# SPI_Switch.net
KiCad netlist of a schematic drawn in EAGLE
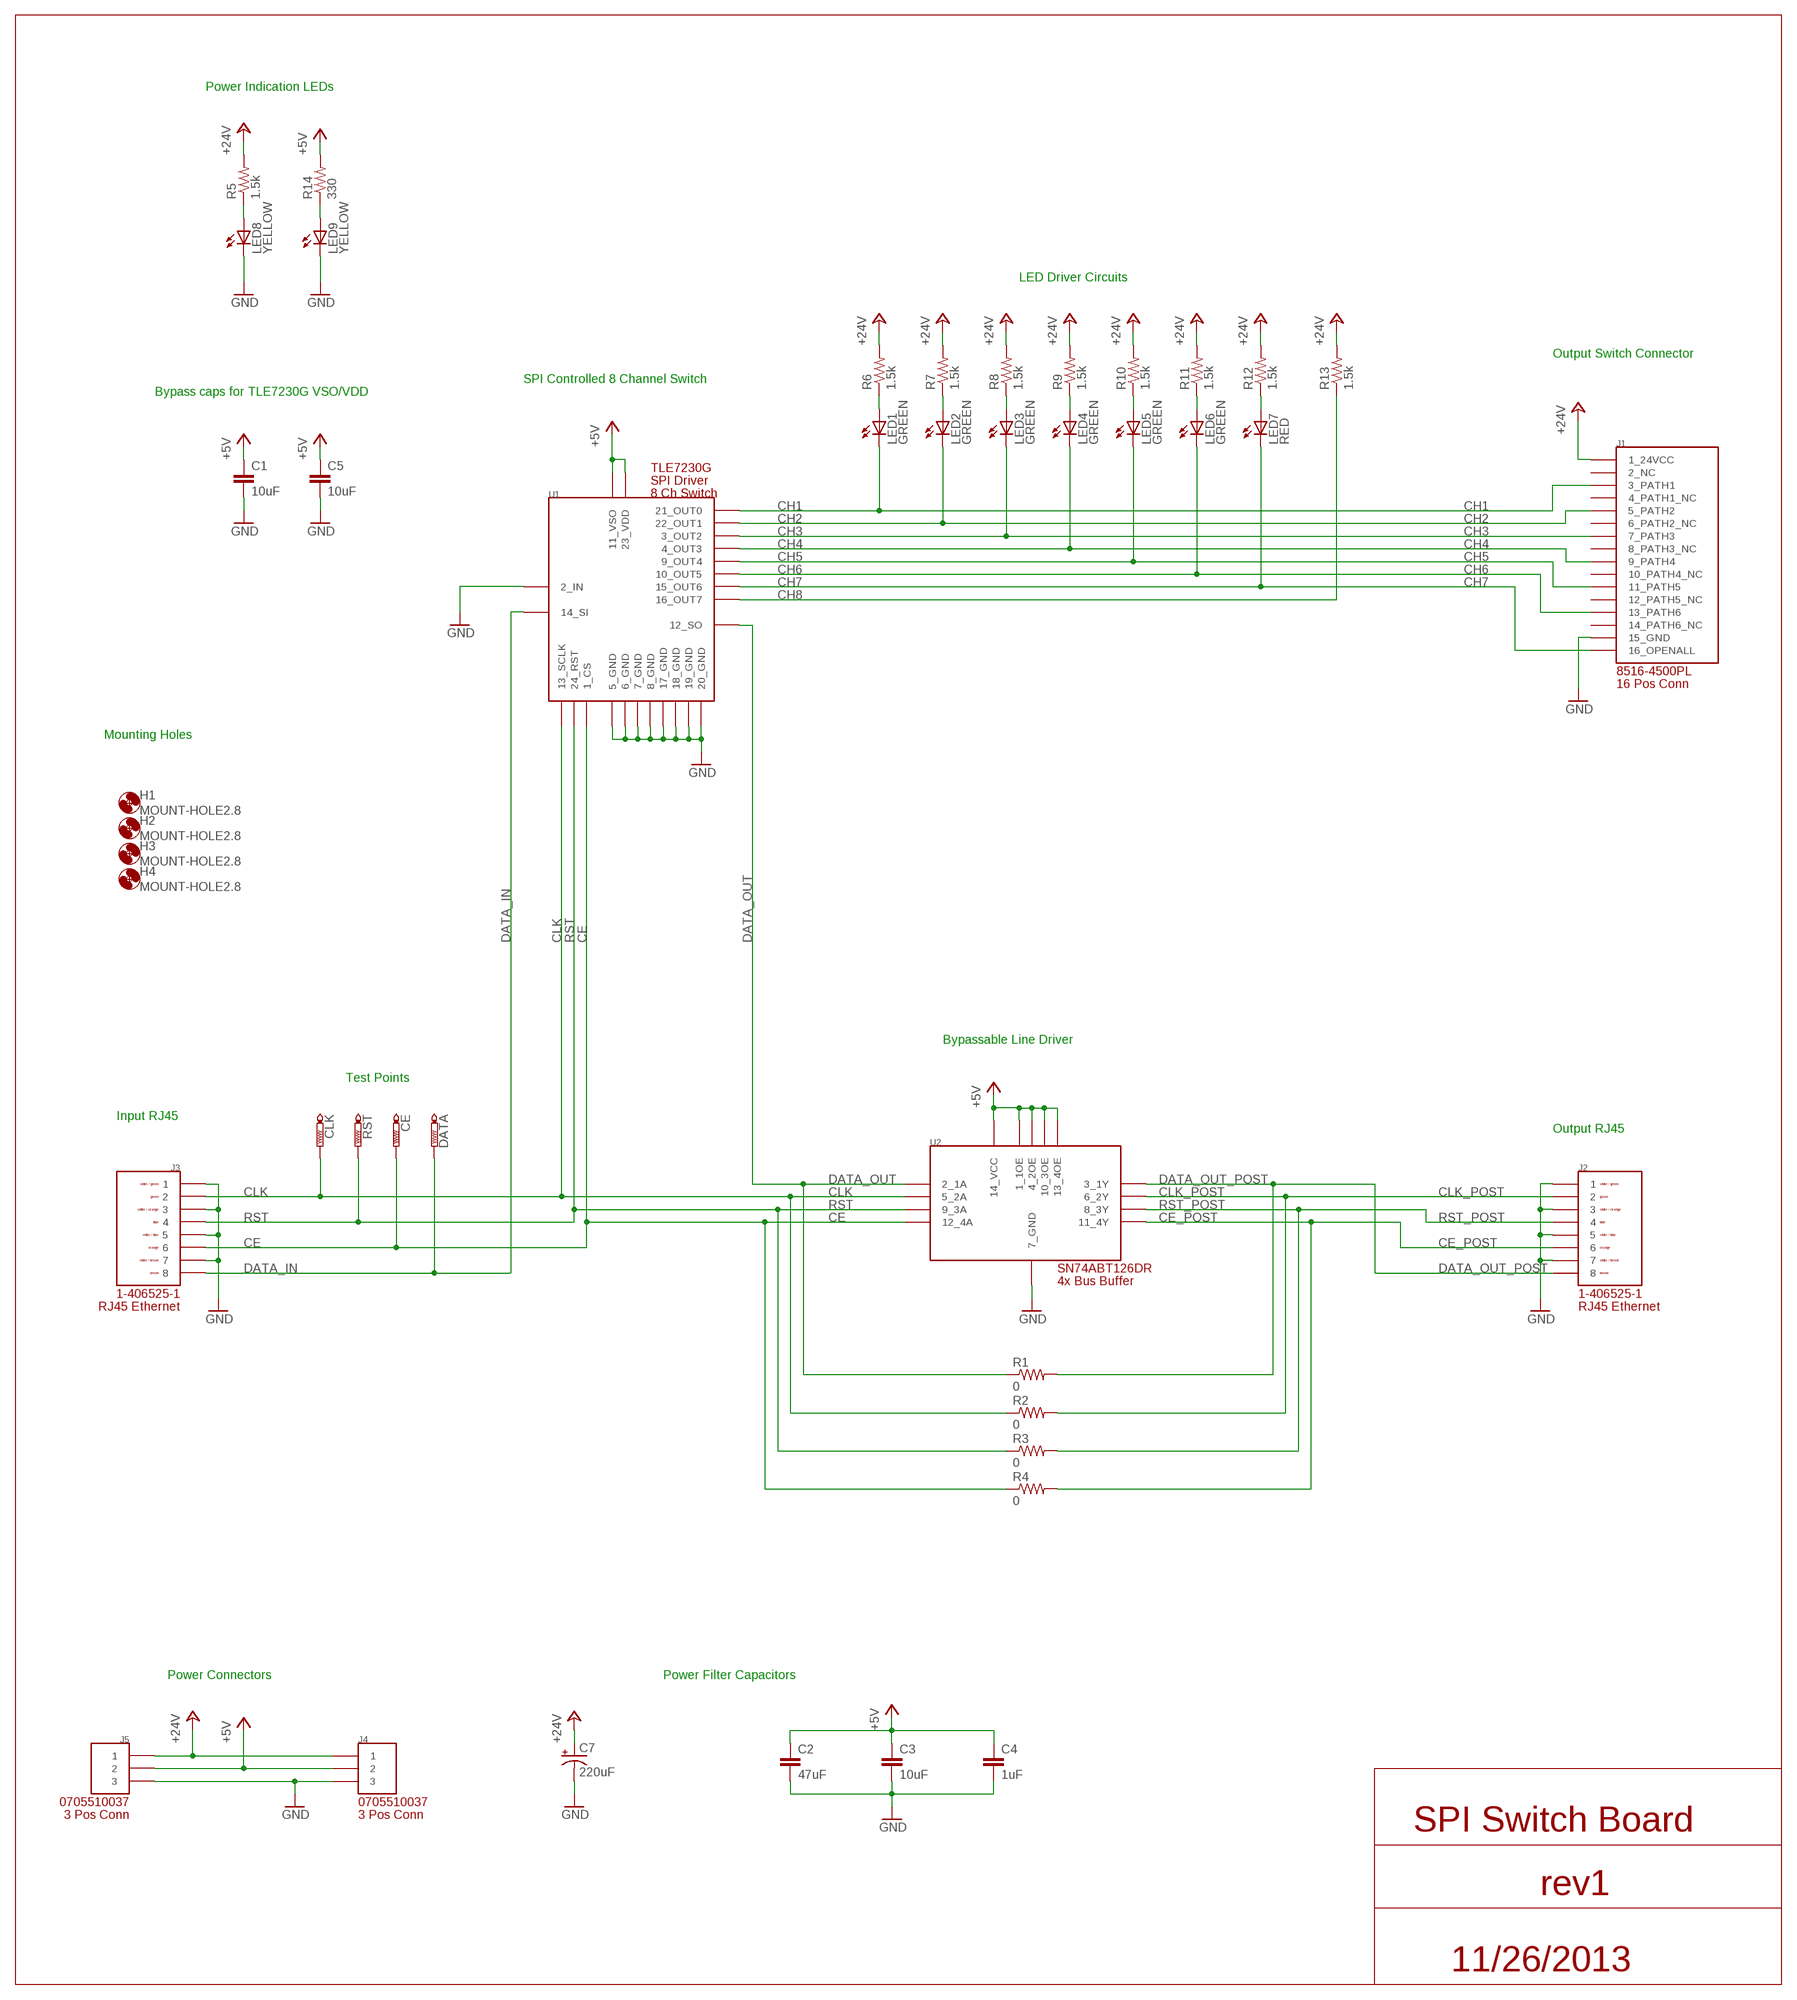
[diagram p0: schematic, sheet 1]

(export (version "E")
  (design (tool "Eeschema 10.0.6"))
  (components
    (comp (ref "C1")
      (value "10uF")
      (footprint "eagle-import:0805")
      (libsource (lib "eagle-import") (part "CAP0805"))
    )
    (comp (ref "C2")
      (value "47uF")
      (footprint "eagle-import:0805")
      (libsource (lib "eagle-import") (part "CAP0805"))
    )
    (comp (ref "C3")
      (value "10uF")
      (footprint "eagle-import:0805")
      (libsource (lib "eagle-import") (part "CAP0805"))
    )
    (comp (ref "C4")
      (value "1uF")
      (footprint "eagle-import:0805")
      (libsource (lib "eagle-import") (part "CAP0805"))
    )
    (comp (ref "C5")
      (value "10uF")
      (footprint "eagle-import:0805")
      (libsource (lib "eagle-import") (part "CAP0805"))
    )
    (comp (ref "C7")
      (value "220uF")
      (footprint "eagle-import:PANASONIC_E")
      (libsource (lib "eagle-import") (part "CAP_POLE"))
    )
    (comp (ref "CE")
      (value "PTR1PAD1-13")
      (footprint "eagle-import:P1-13")
      (libsource (lib "eagle-import") (part "PTR1PAD1-13"))
    )
    (comp (ref "CLK")
      (value "PTR1PAD1-13")
      (footprint "eagle-import:P1-13")
      (libsource (lib "eagle-import") (part "PTR1PAD1-13"))
    )
    (comp (ref "DATA")
      (value "PTR1PAD1-13")
      (footprint "eagle-import:P1-13")
      (libsource (lib "eagle-import") (part "PTR1PAD1-13"))
    )
    (comp (ref "H1")
      (value "MOUNT-HOLE2.8")
      (footprint "eagle-import:2,8")
      (libsource (lib "eagle-import") (part "MOUNT-HOLE2.8"))
    )
    (comp (ref "H2")
      (value "MOUNT-HOLE2.8")
      (footprint "eagle-import:2,8")
      (libsource (lib "eagle-import") (part "MOUNT-HOLE2.8"))
    )
    (comp (ref "H3")
      (value "MOUNT-HOLE2.8")
      (footprint "eagle-import:2,8")
      (libsource (lib "eagle-import") (part "MOUNT-HOLE2.8"))
    )
    (comp (ref "H4")
      (value "MOUNT-HOLE2.8")
      (footprint "eagle-import:2,8")
      (libsource (lib "eagle-import") (part "MOUNT-HOLE2.8"))
    )
    (comp (ref "J1")
      (value "8516-4500PL")
      (footprint "eagle-import:8516-4500PL")
      (libsource (lib "eagle-import") (part "8516-4500PL"))
    )
    (comp (ref "J2")
      (value "1-406525-1")
      (footprint "eagle-import:1-406525-1")
      (libsource (lib "eagle-import") (part "1-406525-1"))
    )
    (comp (ref "J3")
      (value "1-406525-1")
      (footprint "eagle-import:1-406525-1")
      (libsource (lib "eagle-import") (part "1-406525-1"))
    )
    (comp (ref "J4")
      (value "0705510037")
      (footprint "eagle-import:0705510037")
      (libsource (lib "eagle-import") (part "0705510037"))
    )
    (comp (ref "J5")
      (value "0705510037")
      (footprint "eagle-import:0705510037")
      (libsource (lib "eagle-import") (part "0705510037"))
    )
    (comp (ref "LED1")
      (value "GREEN")
      (footprint "eagle-import:LED-1206")
      (libsource (lib "eagle-import") (part "LED1206"))
    )
    (comp (ref "LED2")
      (value "GREEN")
      (footprint "eagle-import:LED-1206")
      (libsource (lib "eagle-import") (part "LED1206"))
    )
    (comp (ref "LED3")
      (value "GREEN")
      (footprint "eagle-import:LED-1206")
      (libsource (lib "eagle-import") (part "LED1206"))
    )
    (comp (ref "LED4")
      (value "GREEN")
      (footprint "eagle-import:LED-1206")
      (libsource (lib "eagle-import") (part "LED1206"))
    )
    (comp (ref "LED5")
      (value "GREEN")
      (footprint "eagle-import:LED-1206")
      (libsource (lib "eagle-import") (part "LED1206"))
    )
    (comp (ref "LED6")
      (value "GREEN")
      (footprint "eagle-import:LED-1206")
      (libsource (lib "eagle-import") (part "LED1206"))
    )
    (comp (ref "LED7")
      (value "RED")
      (footprint "eagle-import:LED-1206")
      (libsource (lib "eagle-import") (part "LED1206"))
    )
    (comp (ref "LED8")
      (value "YELLOW")
      (footprint "eagle-import:LED-1206")
      (libsource (lib "eagle-import") (part "LED1206"))
    )
    (comp (ref "LED9")
      (value "YELLOW")
      (footprint "eagle-import:LED-1206")
      (libsource (lib "eagle-import") (part "LED1206"))
    )
    (comp (ref "R1")
      (value "0")
      (footprint "eagle-import:0805")
      (libsource (lib "eagle-import") (part "RESISTOR0805-RES"))
    )
    (comp (ref "R2")
      (value "0")
      (footprint "eagle-import:0805")
      (libsource (lib "eagle-import") (part "RESISTOR0805-RES"))
    )
    (comp (ref "R3")
      (value "0")
      (footprint "eagle-import:0805")
      (libsource (lib "eagle-import") (part "RESISTOR0805-RES"))
    )
    (comp (ref "R4")
      (value "0")
      (footprint "eagle-import:0805")
      (libsource (lib "eagle-import") (part "RESISTOR0805-RES"))
    )
    (comp (ref "R5")
      (value "1.5k")
      (footprint "eagle-import:1206")
      (libsource (lib "eagle-import") (part "RESISTOR1206"))
    )
    (comp (ref "R6")
      (value "1.5k")
      (footprint "eagle-import:1206")
      (libsource (lib "eagle-import") (part "RESISTOR1206"))
    )
    (comp (ref "R7")
      (value "1.5k")
      (footprint "eagle-import:1206")
      (libsource (lib "eagle-import") (part "RESISTOR1206"))
    )
    (comp (ref "R8")
      (value "1.5k")
      (footprint "eagle-import:1206")
      (libsource (lib "eagle-import") (part "RESISTOR1206"))
    )
    (comp (ref "R9")
      (value "1.5k")
      (footprint "eagle-import:1206")
      (libsource (lib "eagle-import") (part "RESISTOR1206"))
    )
    (comp (ref "R10")
      (value "1.5k")
      (footprint "eagle-import:1206")
      (libsource (lib "eagle-import") (part "RESISTOR1206"))
    )
    (comp (ref "R11")
      (value "1.5k")
      (footprint "eagle-import:1206")
      (libsource (lib "eagle-import") (part "RESISTOR1206"))
    )
    (comp (ref "R12")
      (value "1.5k")
      (footprint "eagle-import:1206")
      (libsource (lib "eagle-import") (part "RESISTOR1206"))
    )
    (comp (ref "R13")
      (value "1.5k")
      (footprint "eagle-import:1206")
      (libsource (lib "eagle-import") (part "RESISTOR1206"))
    )
    (comp (ref "R14")
      (value "330")
      (footprint "eagle-import:0805")
      (libsource (lib "eagle-import") (part "RESISTOR0805-RES"))
    )
    (comp (ref "RST")
      (value "PTR1PAD1-13")
      (footprint "eagle-import:P1-13")
      (libsource (lib "eagle-import") (part "PTR1PAD1-13"))
    )
    (comp (ref "U1")
      (value "TLE7230G")
      (footprint "eagle-import:TLE7230G")
      (libsource (lib "eagle-import") (part "TLE7230G"))
    )
    (comp (ref "U2")
      (value "SN74ABT126")
      (footprint "eagle-import:SN74ABT126")
      (libsource (lib "eagle-import") (part "SN74ABT126"))
    )
  )
  (nets
    (net (code "1") (name "+5V") (class "Default")
      (node (ref "C1") (pin "1") (pinfunction "1_1") (pintype "passive"))
      (node (ref "C2") (pin "1") (pinfunction "1_1") (pintype "passive"))
      (node (ref "C3") (pin "1") (pinfunction "1_1") (pintype "passive"))
      (node (ref "C4") (pin "1") (pinfunction "1_1") (pintype "passive"))
      (node (ref "C5") (pin "1") (pinfunction "1_1") (pintype "passive"))
      (node (ref "J4") (pin "P$2") (pinfunction "2_P$2") (pintype "bidirectional"))
      (node (ref "J5") (pin "P$2") (pinfunction "2_P$2") (pintype "bidirectional"))
      (node (ref "R14") (pin "2") (pinfunction "2_2") (pintype "passive"))
      (node (ref "U1") (pin "11") (pinfunction "11_VSO_11") (pintype "bidirectional"))
      (node (ref "U1") (pin "23") (pinfunction "23_VDD_23") (pintype "bidirectional"))
      (node (ref "U2") (pin "1") (pinfunction "1_1OE_1") (pintype "bidirectional"))
      (node (ref "U2") (pin "10") (pinfunction "10_3OE_10") (pintype "bidirectional"))
      (node (ref "U2") (pin "13") (pinfunction "13_4OE_13") (pintype "bidirectional"))
      (node (ref "U2") (pin "14") (pinfunction "14_VCC_14") (pintype "bidirectional"))
      (node (ref "U2") (pin "4") (pinfunction "4_2OE_4") (pintype "bidirectional"))
    )
    (net (code "2") (name "+24V") (class "Default")
      (node (ref "C7") (pin "+") (pinfunction "+_+") (pintype "passive"))
      (node (ref "J1") (pin "P$1") (pinfunction "1_24VCC_P$1") (pintype "bidirectional"))
      (node (ref "J4") (pin "P$1") (pinfunction "1_P$1") (pintype "bidirectional"))
      (node (ref "J5") (pin "P$1") (pinfunction "1_P$1") (pintype "bidirectional"))
      (node (ref "R10") (pin "2") (pinfunction "2_2") (pintype "passive"))
      (node (ref "R11") (pin "2") (pinfunction "2_2") (pintype "passive"))
      (node (ref "R12") (pin "2") (pinfunction "2_2") (pintype "passive"))
      (node (ref "R13") (pin "2") (pinfunction "2_2") (pintype "passive"))
      (node (ref "R5") (pin "2") (pinfunction "2_2") (pintype "passive"))
      (node (ref "R6") (pin "2") (pinfunction "2_2") (pintype "passive"))
      (node (ref "R7") (pin "2") (pinfunction "2_2") (pintype "passive"))
      (node (ref "R8") (pin "2") (pinfunction "2_2") (pintype "passive"))
      (node (ref "R9") (pin "2") (pinfunction "2_2") (pintype "passive"))
    )
    (net (code "3") (name "/CE") (class "Default")
      (node (ref "CE") (pin "TP") (pinfunction "TP_TP") (pintype "input"))
      (node (ref "J3") (pin "P$6") (pinfunction "6_P$6") (pintype "bidirectional"))
      (node (ref "R4") (pin "1") (pinfunction "1_1") (pintype "passive"))
      (node (ref "U1") (pin "1") (pinfunction "1_CS_1") (pintype "bidirectional"))
      (node (ref "U2") (pin "12") (pinfunction "12_4A_12") (pintype "bidirectional"))
    )
    (net (code "4") (name "/CE_POST") (class "Default")
      (node (ref "J2") (pin "P$6") (pinfunction "6_P$6") (pintype "bidirectional"))
      (node (ref "R4") (pin "2") (pinfunction "2_2") (pintype "passive"))
      (node (ref "U2") (pin "11") (pinfunction "11_4Y_11") (pintype "bidirectional"))
    )
    (net (code "5") (name "/CH1") (class "Default")
      (node (ref "J1") (pin "P$3") (pinfunction "3_PATH1_P$3") (pintype "bidirectional"))
      (node (ref "LED1") (pin "C") (pinfunction "C_C") (pintype "passive"))
      (node (ref "U1") (pin "21") (pinfunction "21_OUT0_21") (pintype "bidirectional"))
    )
    (net (code "6") (name "/CH2") (class "Default")
      (node (ref "J1") (pin "P$5") (pinfunction "5_PATH2_P$5") (pintype "bidirectional"))
      (node (ref "LED2") (pin "C") (pinfunction "C_C") (pintype "passive"))
      (node (ref "U1") (pin "22") (pinfunction "22_OUT1_22") (pintype "bidirectional"))
    )
    (net (code "7") (name "/CH3") (class "Default")
      (node (ref "J1") (pin "P$7") (pinfunction "7_PATH3_P$7") (pintype "bidirectional"))
      (node (ref "LED3") (pin "C") (pinfunction "C_C") (pintype "passive"))
      (node (ref "U1") (pin "3") (pinfunction "3_OUT2_3") (pintype "bidirectional"))
    )
    (net (code "8") (name "/CH4") (class "Default")
      (node (ref "J1") (pin "P$9") (pinfunction "9_PATH4_P$9") (pintype "bidirectional"))
      (node (ref "LED4") (pin "C") (pinfunction "C_C") (pintype "passive"))
      (node (ref "U1") (pin "4") (pinfunction "4_OUT3_4") (pintype "bidirectional"))
    )
    (net (code "9") (name "/CH5") (class "Default")
      (node (ref "J1") (pin "P$11") (pinfunction "11_PATH5_P$11") (pintype "bidirectional"))
      (node (ref "LED5") (pin "C") (pinfunction "C_C") (pintype "passive"))
      (node (ref "U1") (pin "9") (pinfunction "9_OUT4_9") (pintype "bidirectional"))
    )
    (net (code "10") (name "/CH6") (class "Default")
      (node (ref "J1") (pin "P$13") (pinfunction "13_PATH6_P$13") (pintype "bidirectional"))
      (node (ref "LED6") (pin "C") (pinfunction "C_C") (pintype "passive"))
      (node (ref "U1") (pin "10") (pinfunction "10_OUT5_10") (pintype "bidirectional"))
    )
    (net (code "11") (name "/CH7") (class "Default")
      (node (ref "J1") (pin "P$16") (pinfunction "16_OPENALL_P$16") (pintype "bidirectional"))
      (node (ref "LED7") (pin "C") (pinfunction "C_C") (pintype "passive"))
      (node (ref "U1") (pin "15") (pinfunction "15_OUT6_15") (pintype "bidirectional"))
    )
    (net (code "12") (name "/CH8") (class "Default")
      (node (ref "R13") (pin "1") (pinfunction "1_1") (pintype "passive"))
      (node (ref "U1") (pin "16") (pinfunction "16_OUT7_16") (pintype "bidirectional"))
    )
    (net (code "13") (name "/CLK") (class "Default")
      (node (ref "CLK") (pin "TP") (pinfunction "TP_TP") (pintype "input"))
      (node (ref "J3") (pin "P$2") (pinfunction "2_P$2") (pintype "bidirectional"))
      (node (ref "R2") (pin "1") (pinfunction "1_1") (pintype "passive"))
      (node (ref "U1") (pin "13") (pinfunction "13_SCLK_13") (pintype "bidirectional"))
      (node (ref "U2") (pin "5") (pinfunction "5_2A_5") (pintype "bidirectional"))
    )
    (net (code "14") (name "/CLK_POST") (class "Default")
      (node (ref "J2") (pin "P$2") (pinfunction "2_P$2") (pintype "bidirectional"))
      (node (ref "R2") (pin "2") (pinfunction "2_2") (pintype "passive"))
      (node (ref "U2") (pin "6") (pinfunction "6_2Y_6") (pintype "bidirectional"))
    )
    (net (code "15") (name "/DATA_IN") (class "Default")
      (node (ref "DATA") (pin "TP") (pinfunction "TP_TP") (pintype "input"))
      (node (ref "J3") (pin "P$8") (pinfunction "8_P$8") (pintype "bidirectional"))
      (node (ref "U1") (pin "14") (pinfunction "14_SI_14") (pintype "bidirectional"))
    )
    (net (code "16") (name "/DATA_OUT") (class "Default")
      (node (ref "R1") (pin "1") (pinfunction "1_1") (pintype "passive"))
      (node (ref "U1") (pin "12") (pinfunction "12_SO_12") (pintype "bidirectional"))
      (node (ref "U2") (pin "2") (pinfunction "2_1A_2") (pintype "bidirectional"))
    )
    (net (code "17") (name "/DATA_OUT_POST") (class "Default")
      (node (ref "J2") (pin "P$8") (pinfunction "8_P$8") (pintype "bidirectional"))
      (node (ref "R1") (pin "2") (pinfunction "2_2") (pintype "passive"))
      (node (ref "U2") (pin "3") (pinfunction "3_1Y_3") (pintype "bidirectional"))
    )
    (net (code "18") (name "/RST") (class "Default")
      (node (ref "J3") (pin "P$4") (pinfunction "4_P$4") (pintype "bidirectional"))
      (node (ref "R3") (pin "1") (pinfunction "1_1") (pintype "passive"))
      (node (ref "RST") (pin "TP") (pinfunction "TP_TP") (pintype "input"))
      (node (ref "U1") (pin "24") (pinfunction "24_RST_24") (pintype "bidirectional"))
      (node (ref "U2") (pin "9") (pinfunction "9_3A_9") (pintype "bidirectional"))
    )
    (net (code "19") (name "/RST_POST") (class "Default")
      (node (ref "J2") (pin "P$4") (pinfunction "4_P$4") (pintype "bidirectional"))
      (node (ref "R3") (pin "2") (pinfunction "2_2") (pintype "passive"))
      (node (ref "U2") (pin "8") (pinfunction "8_3Y_8") (pintype "bidirectional"))
    )
    (net (code "20") (name "GND") (class "Default")
      (node (ref "C1") (pin "2") (pinfunction "2_2") (pintype "passive"))
      (node (ref "C2") (pin "2") (pinfunction "2_2") (pintype "passive"))
      (node (ref "C3") (pin "2") (pinfunction "2_2") (pintype "passive"))
      (node (ref "C4") (pin "2") (pinfunction "2_2") (pintype "passive"))
      (node (ref "C5") (pin "2") (pinfunction "2_2") (pintype "passive"))
      (node (ref "C7") (pin "-") (pinfunction "-_-") (pintype "passive"))
      (node (ref "J1") (pin "P$15") (pinfunction "15_GND_P$15") (pintype "bidirectional"))
      (node (ref "J2") (pin "P$1") (pinfunction "1_P$1") (pintype "bidirectional"))
      (node (ref "J2") (pin "P$3") (pinfunction "3_P$3") (pintype "bidirectional"))
      (node (ref "J2") (pin "P$5") (pinfunction "5_P$5") (pintype "bidirectional"))
      (node (ref "J2") (pin "P$7") (pinfunction "7_P$7") (pintype "bidirectional"))
      (node (ref "J3") (pin "P$1") (pinfunction "1_P$1") (pintype "bidirectional"))
      (node (ref "J3") (pin "P$3") (pinfunction "3_P$3") (pintype "bidirectional"))
      (node (ref "J3") (pin "P$5") (pinfunction "5_P$5") (pintype "bidirectional"))
      (node (ref "J3") (pin "P$7") (pinfunction "7_P$7") (pintype "bidirectional"))
      (node (ref "J4") (pin "P$3") (pinfunction "3_P$3") (pintype "bidirectional"))
      (node (ref "J5") (pin "P$3") (pinfunction "3_P$3") (pintype "bidirectional"))
      (node (ref "LED8") (pin "C") (pinfunction "C_C") (pintype "passive"))
      (node (ref "LED9") (pin "C") (pinfunction "C_C") (pintype "passive"))
      (node (ref "U1") (pin "17") (pinfunction "17_GND_17") (pintype "bidirectional"))
      (node (ref "U1") (pin "18") (pinfunction "18_GND_18") (pintype "bidirectional"))
      (node (ref "U1") (pin "19") (pinfunction "19_GND_19") (pintype "bidirectional"))
      (node (ref "U1") (pin "2") (pinfunction "2_IN_2") (pintype "bidirectional"))
      (node (ref "U1") (pin "20") (pinfunction "20_GND_20") (pintype "bidirectional"))
      (node (ref "U1") (pin "5") (pinfunction "5_GND_5") (pintype "bidirectional"))
      (node (ref "U1") (pin "6") (pinfunction "6_GND_6") (pintype "bidirectional"))
      (node (ref "U1") (pin "7") (pinfunction "7_GND_7") (pintype "bidirectional"))
      (node (ref "U1") (pin "8") (pinfunction "8_GND_8") (pintype "bidirectional"))
      (node (ref "U2") (pin "7") (pinfunction "7_GND_7") (pintype "bidirectional"))
    )
    (net (code "21") (name "Net-(LED1-PadA)") (class "Default")
      (node (ref "LED1") (pin "A") (pinfunction "A_A") (pintype "passive"))
      (node (ref "R6") (pin "1") (pinfunction "1_1") (pintype "passive"))
    )
    (net (code "22") (name "Net-(LED2-PadA)") (class "Default")
      (node (ref "LED2") (pin "A") (pinfunction "A_A") (pintype "passive"))
      (node (ref "R7") (pin "1") (pinfunction "1_1") (pintype "passive"))
    )
    (net (code "23") (name "Net-(LED3-PadA)") (class "Default")
      (node (ref "LED3") (pin "A") (pinfunction "A_A") (pintype "passive"))
      (node (ref "R8") (pin "1") (pinfunction "1_1") (pintype "passive"))
    )
    (net (code "24") (name "Net-(LED4-PadA)") (class "Default")
      (node (ref "LED4") (pin "A") (pinfunction "A_A") (pintype "passive"))
      (node (ref "R9") (pin "1") (pinfunction "1_1") (pintype "passive"))
    )
    (net (code "25") (name "Net-(LED5-PadA)") (class "Default")
      (node (ref "LED5") (pin "A") (pinfunction "A_A") (pintype "passive"))
      (node (ref "R10") (pin "1") (pinfunction "1_1") (pintype "passive"))
    )
    (net (code "26") (name "Net-(LED6-PadA)") (class "Default")
      (node (ref "LED6") (pin "A") (pinfunction "A_A") (pintype "passive"))
      (node (ref "R11") (pin "1") (pinfunction "1_1") (pintype "passive"))
    )
    (net (code "27") (name "Net-(LED7-PadA)") (class "Default")
      (node (ref "LED7") (pin "A") (pinfunction "A_A") (pintype "passive"))
      (node (ref "R12") (pin "1") (pinfunction "1_1") (pintype "passive"))
    )
    (net (code "28") (name "Net-(LED8-PadA)") (class "Default")
      (node (ref "LED8") (pin "A") (pinfunction "A_A") (pintype "passive"))
      (node (ref "R5") (pin "1") (pinfunction "1_1") (pintype "passive"))
    )
    (net (code "29") (name "Net-(LED9-PadA)") (class "Default")
      (node (ref "LED9") (pin "A") (pinfunction "A_A") (pintype "passive"))
      (node (ref "R14") (pin "1") (pinfunction "1_1") (pintype "passive"))
    )
    (net (code "30") (name "unconnected-(J1-2_NC-PadP$2)") (class "Default")
      (node (ref "J1") (pin "P$2") (pinfunction "2_NC_P$2") (pintype "no_connect"))
    )
    (net (code "31") (name "unconnected-(J1-4_PATH1_NC-PadP$4)") (class "Default")
      (node (ref "J1") (pin "P$4") (pinfunction "4_PATH1_NC_P$4") (pintype "no_connect"))
    )
    (net (code "32") (name "unconnected-(J1-6_PATH2_NC-PadP$6)") (class "Default")
      (node (ref "J1") (pin "P$6") (pinfunction "6_PATH2_NC_P$6") (pintype "no_connect"))
    )
    (net (code "33") (name "unconnected-(J1-8_PATH3_NC-PadP$8)") (class "Default")
      (node (ref "J1") (pin "P$8") (pinfunction "8_PATH3_NC_P$8") (pintype "no_connect"))
    )
    (net (code "34") (name "unconnected-(J1-10_PATH4_NC-PadP$10)") (class "Default")
      (node (ref "J1") (pin "P$10") (pinfunction "10_PATH4_NC_P$10") (pintype "no_connect"))
    )
    (net (code "35") (name "unconnected-(J1-12_PATH5_NC-PadP$12)") (class "Default")
      (node (ref "J1") (pin "P$12") (pinfunction "12_PATH5_NC_P$12") (pintype "no_connect"))
    )
    (net (code "36") (name "unconnected-(J1-14_PATH6_NC-PadP$14)") (class "Default")
      (node (ref "J1") (pin "P$14") (pinfunction "14_PATH6_NC_P$14") (pintype "no_connect"))
    )
  )
)
